# IO.net
KiCad netlist of a schematic drawn in Altium Designer
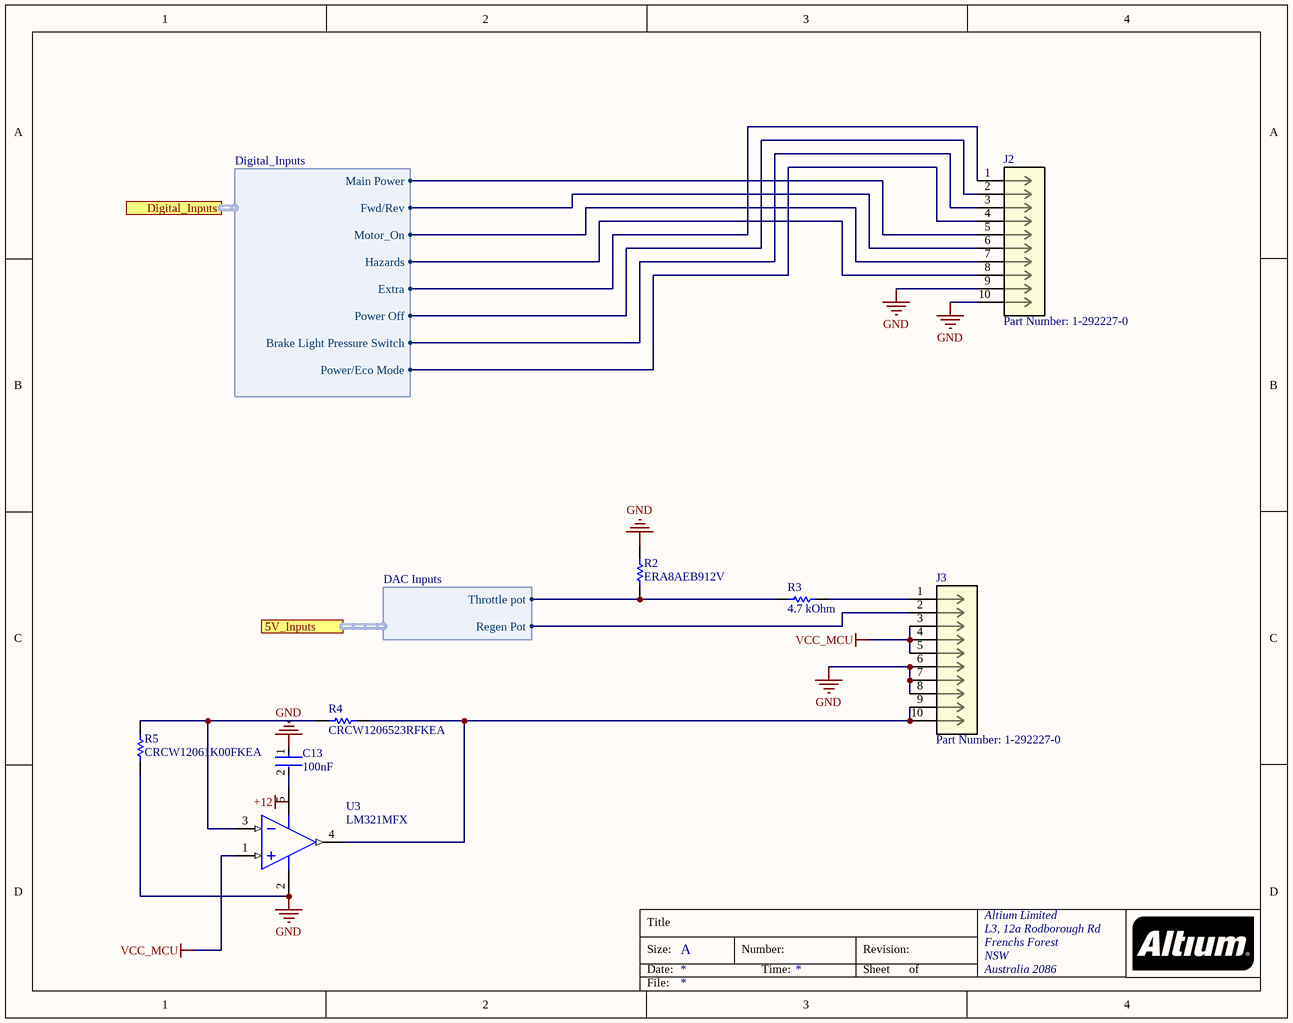
[diagram p0: IO.SchDoc]

(export (version "E")
  (design (tool "Eeschema 10.0.6"))
  (components
    (comp (ref "C13")
      (value "100nF")
      (footprint "Kemet_C0603_IPC_A")
      (description "CAP CER 0.1UF 100NF 50V X7R 0603 C0603C104K5RACTU")
      (libsource (lib "UNK_Kemet_C0603C104K5RACTU_eec") (part "C0603C104K5RACTU"))
    )
    (comp (ref "J2")
      (value "Part Number: 1-292227-0")
      (footprint "CON10_1X10_DRH_H")
      (description "No Description Available")
      (fields
        (field (name "MANUFACTURER_PART_NUMBER") "1-292227-0")
        (field (name "COPYRIGHT") "Copyright (C) 2018 Accelerated Designs. All rights reserved")
      )
      (libsource (lib "AMP_MINI_CT_10PIN") (part "1-292227-0"))
    )
    (comp (ref "J3")
      (value "Part Number: 1-292227-0")
      (footprint "CON10_1X10_DRH_H")
      (description "No Description Available")
      (fields
        (field (name "MANUFACTURER_PART_NUMBER") "1-292227-0")
        (field (name "COPYRIGHT") "Copyright (C) 2018 Accelerated Designs. All rights reserved")
      )
      (libsource (lib "AMP_MINI_CT_10PIN") (part "1-292227-0"))
    )
    (comp (ref "R2")
      (value "ERA8AEB912V")
      (footprint "RESC3216X70X50ML20T25")
      (fields (field (name "MANUFACTURER") "Panasonic"))
      (libsource (lib "Altium Content Vault") (part "RES"))
    )
    (comp (ref "R3")
      (value "4.7 kOhm")
      (footprint "RESC3216X60X45ML15T20")
      (description "Chip Resistor, 4.7 KOhm, +/- 1%, 0.25 W, -55 to 155 degC, 1206 (3216 Metric), RoHS, Tape and Reel")
      (fields (field (name "MANUFACTURER") "Vishay Semiconductor") (field (name "TOLERANCE") "1%"))
      (libsource (lib "Altium Content Vault") (part "RES-2"))
    )
    (comp (ref "R4")
      (value "CRCW1206523RFKEA")
      (footprint "RESC3216X60X45NL10T20")
      (fields (field (name "MANUFACTURER") "Vishay Dale"))
      (libsource (lib "Altium Content Vault") (part "RES"))
    )
    (comp (ref "R5")
      (value "CRCW12061K00FKEA")
      (footprint "RESC3216X60X45ML15T20")
      (description "Chip Resistor, 1 KOhm, +/- 1%, 0.25 W, -55 to 155 degC, 1206 (3216 Metric), RoHS, Tape and Reel")
      (fields (field (name "MANUFACTURER") "Vishay Semiconductor") (field (name "TOLERANCE") "1%"))
      (libsource (lib "Altium Content Vault") (part "RES-2"))
    )
    (comp (ref "U3")
      (value "LM321MFX")
      (footprint "DBV0005A_L")
      (description "Low Power Single Op Amp, 5-pin SOT-23")
      (fields (field (name "MANUFACTURER") "Texas Instruments"))
      (libsource (lib "Altium Content Vault") (part "AMP-OPA-LMV551-5"))
    )
  )
  (nets
    (net (code "5") (name "/Brake Light Pressure Switch") (class "Default")
      (node (ref "J2") (pin "3") (pinfunction "3_3") (pintype "passive"))
    )
    (net (code "6") (name "/Extra") (class "Default")
      (node (ref "J2") (pin "1") (pinfunction "1_1") (pintype "passive"))
    )
    (net (code "7") (name "/Fwd{slash}Rev") (class "Default")
      (node (ref "J2") (pin "6") (pinfunction "6_6") (pintype "passive"))
    )
    (net (code "8") (name "/Hazards") (class "Default")
      (node (ref "J2") (pin "8") (pinfunction "8_8") (pintype "passive"))
    )
    (net (code "9") (name "/Main Power") (class "Default")
      (node (ref "J2") (pin "5") (pinfunction "5_5") (pintype "passive"))
    )
    (net (code "10") (name "/Motor_On") (class "Default")
      (node (ref "J2") (pin "7") (pinfunction "7_7") (pintype "passive"))
    )
    (net (code "11") (name "/Power Off") (class "Default")
      (node (ref "J2") (pin "2") (pinfunction "2_2") (pintype "passive"))
    )
    (net (code "12") (name "/Power{slash}Eco Mode") (class "Default")
      (node (ref "J2") (pin "4") (pinfunction "4_4") (pintype "passive"))
    )
    (net (code "13") (name "/Regen Pot") (class "Default")
      (node (ref "J3") (pin "2") (pinfunction "2_2") (pintype "passive"))
    )
    (net (code "14") (name "/Throttle pot") (class "Default")
      (node (ref "R2") (pin "2") (pinfunction "2_2") (pintype "passive"))
      (node (ref "R3") (pin "2") (pinfunction "2_2") (pintype "passive"))
    )
    (net (code "17") (name "GND") (class "Default")
      (node (ref "C13") (pin "1") (pinfunction "1_1") (pintype "passive"))
      (node (ref "J2") (pin "10") (pinfunction "10_10") (pintype "passive"))
      (node (ref "J2") (pin "9") (pinfunction "9_9") (pintype "passive"))
      (node (ref "J3") (pin "6") (pinfunction "6_6") (pintype "passive"))
      (node (ref "J3") (pin "7") (pinfunction "7_7") (pintype "passive"))
      (node (ref "J3") (pin "8") (pinfunction "8_8") (pintype "passive"))
      (node (ref "R2") (pin "1") (pinfunction "1_1") (pintype "passive"))
      (node (ref "R5") (pin "2") (pinfunction "2_2") (pintype "passive"))
      (node (ref "U3") (pin "2") (pinfunction "V-_2") (pintype "power_in"))
    )
    (net (code "18") (name "Net-(J3-Pad1)") (class "Default")
      (node (ref "J3") (pin "1") (pinfunction "1_1") (pintype "passive"))
      (node (ref "R3") (pin "1") (pinfunction "1_1") (pintype "passive"))
    )
    (net (code "19") (name "Net-(U3-IN-)") (class "Default")
      (node (ref "R4") (pin "2") (pinfunction "2_2") (pintype "passive"))
      (node (ref "R5") (pin "1") (pinfunction "1_1") (pintype "passive"))
      (node (ref "U3") (pin "3") (pinfunction "IN-_3") (pintype "input"))
    )
    (net (code "20") (name "Net-(U3-OUT)") (class "Default")
      (node (ref "J3") (pin "10") (pinfunction "10_10") (pintype "passive"))
      (node (ref "J3") (pin "9") (pinfunction "9_9") (pintype "passive"))
      (node (ref "R4") (pin "1") (pinfunction "1_1") (pintype "passive"))
      (node (ref "U3") (pin "4") (pinfunction "OUT_4") (pintype "output"))
    )
    (net (code "21") (name "Net-(U3-V+)") (class "Default")
      (node (ref "C13") (pin "2") (pinfunction "2_2") (pintype "passive"))
      (node (ref "U3") (pin "5") (pinfunction "V+_5") (pintype "power_in"))
    )
    (net (code "22") (name "VCC_MCU") (class "Default")
      (node (ref "J3") (pin "3") (pinfunction "3_3") (pintype "passive"))
      (node (ref "J3") (pin "4") (pinfunction "4_4") (pintype "passive"))
      (node (ref "J3") (pin "5") (pinfunction "5_5") (pintype "passive"))
      (node (ref "U3") (pin "1") (pinfunction "IN+_1") (pintype "input"))
    )
  )
)
